# SensWear_Debug.net
KiCad netlist of a schematic drawn in Altium Designer
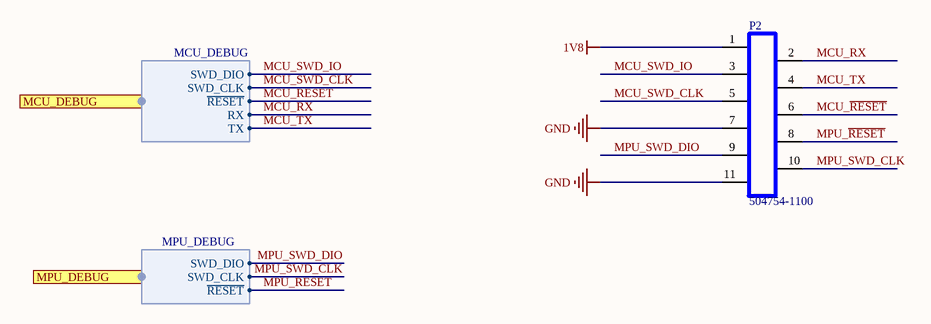
[diagram p0: SensWear_Debug.SchDoc]

(export (version "E")
  (design (tool "Eeschema 10.0.6"))
  (components
    (comp (ref "P2")
      (value "504754-1100")
      (footprint "5047541100")
      (description "Conn FFC/FPC Connector SKT 11 POS 0.3mm Solder RA SMD Easy-On™ T/R")
      (fields (field (name "MANUFACTURER") "Molex") (field (name "CHECKED") "FALSE"))
      (libsource (lib "Connectors") (part "504754-1100"))
    )
  )
  (nets
    (net (code "3") (name "/MCU_RX") (class "Default")
      (node (ref "P2") (pin "2") (pinfunction "2_2") (pintype "passive"))
    )
    (net (code "4") (name "/MCU_SWD_CLK") (class "Default")
      (node (ref "P2") (pin "5") (pinfunction "5_5") (pintype "passive"))
    )
    (net (code "5") (name "/MCU_SWD_IO") (class "Default")
      (node (ref "P2") (pin "3") (pinfunction "3_3") (pintype "passive"))
    )
    (net (code "6") (name "/MCU_TX") (class "Default")
      (node (ref "P2") (pin "4") (pinfunction "4_4") (pintype "passive"))
    )
    (net (code "7") (name "/MCU_~{RESET}") (class "Default")
      (node (ref "P2") (pin "6") (pinfunction "6_6") (pintype "passive"))
    )
    (net (code "8") (name "/MPU_SWD_CLK") (class "Default")
      (node (ref "P2") (pin "10") (pinfunction "10_10") (pintype "passive"))
    )
    (net (code "9") (name "/MPU_SWD_DIO") (class "Default")
      (node (ref "P2") (pin "9") (pinfunction "9_9") (pintype "passive"))
    )
    (net (code "10") (name "/MPU_~{RESET}") (class "Default")
      (node (ref "P2") (pin "8") (pinfunction "8_8") (pintype "passive"))
    )
    (net (code "13") (name "1V8") (class "Default")
      (node (ref "P2") (pin "1") (pinfunction "1_1") (pintype "passive"))
    )
    (net (code "14") (name "GND") (class "Default")
      (node (ref "P2") (pin "11") (pinfunction "11_11") (pintype "passive"))
      (node (ref "P2") (pin "7") (pinfunction "7_7") (pintype "passive"))
    )
  )
)
